# CH32M030K8U7-R0.net
KiCad netlist of a schematic drawn in Altium Designer
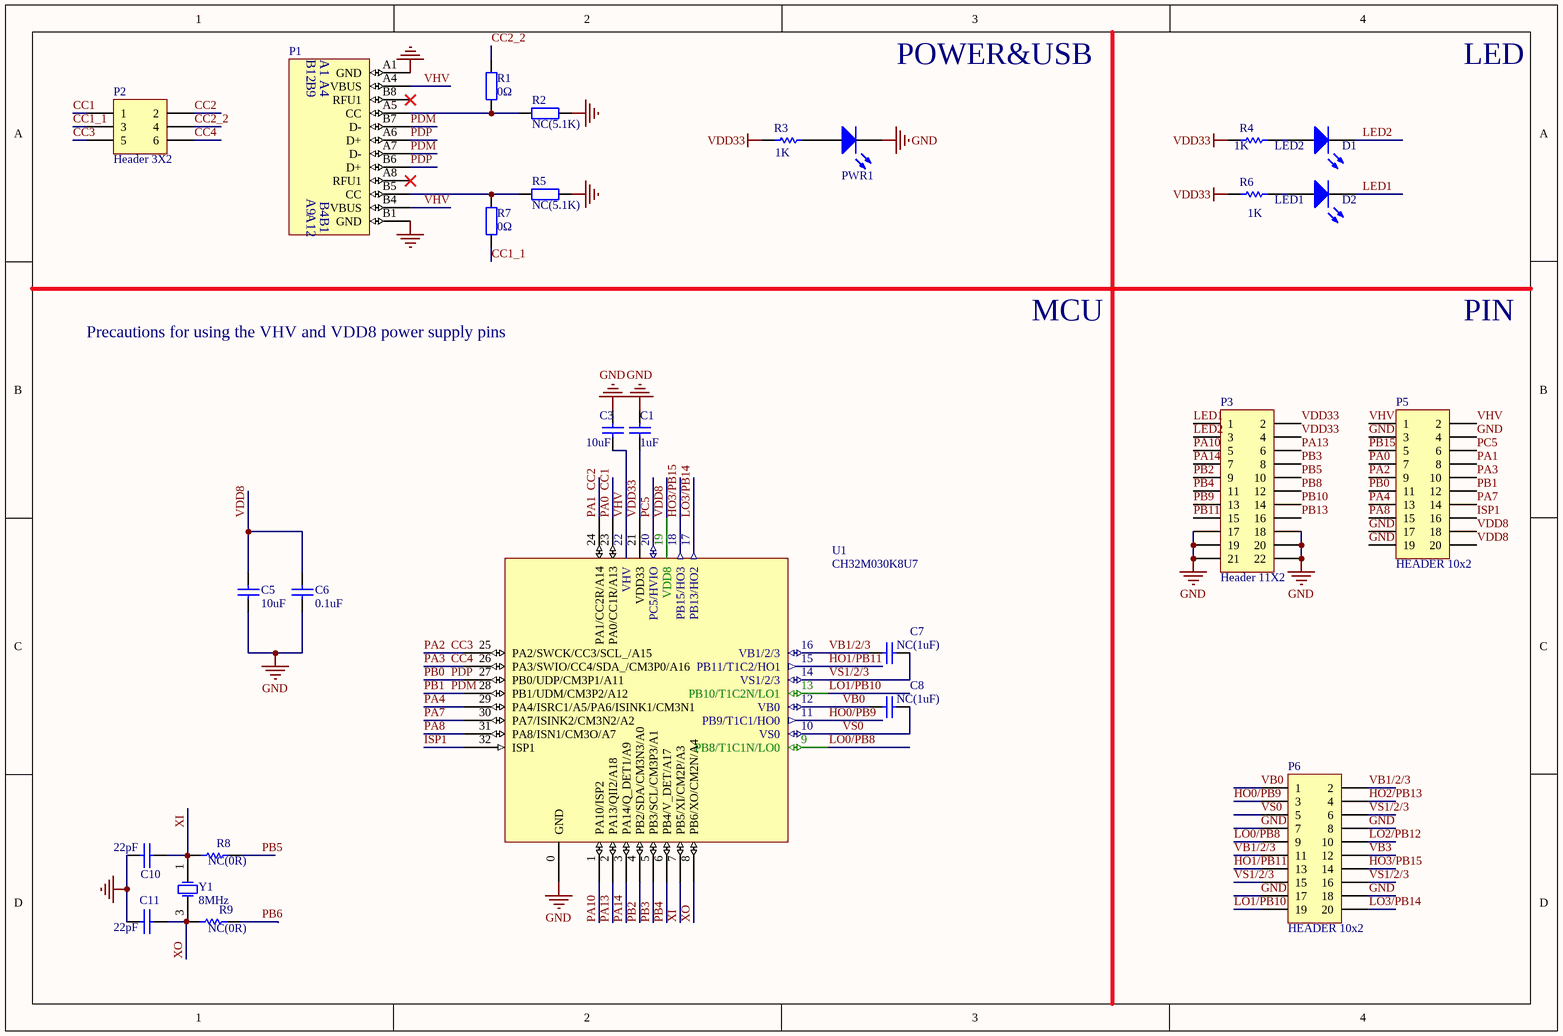
[diagram p0: CH32M030K8U7-R0.SchDoc]

(export (version "E")
  (design (tool "Eeschema 10.0.6"))
  (components
    (comp (ref "C1")
      (value "1uF")
      (footprint "0603_C")
      (description "Capacitor")
      (fields (field (name "PUBLISHER") "Altium Limited"))
      (libsource (lib "*") (part "Cap"))
    )
    (comp (ref "C3")
      (value "10uF")
      (footprint "0603_C")
      (description "Capacitor")
      (fields (field (name "PUBLISHER") "Altium Limited"))
      (libsource (lib "*") (part "Cap"))
    )
    (comp (ref "C5")
      (value "10uF")
      (footprint "0603_C")
      (description "Capacitor")
      (fields (field (name "PUBLISHER") "Altium Limited"))
      (libsource (lib "*") (part "Cap"))
    )
    (comp (ref "C6")
      (value "0.1uF")
      (footprint "0603_C")
      (description "Capacitor")
      (fields (field (name "PUBLISHER") "Altium Limited"))
      (libsource (lib "*") (part "Cap"))
    )
    (comp (ref "C7")
      (value "NC(1uF)")
      (footprint "0603_C")
      (description "Capacitor")
      (fields (field (name "PUBLISHER") "Altium Limited"))
      (libsource (lib "*") (part "Cap"))
    )
    (comp (ref "C8")
      (value "NC(1uF)")
      (footprint "0603_C")
      (description "Capacitor")
      (fields (field (name "PUBLISHER") "Altium Limited"))
      (libsource (lib "*") (part "Cap"))
    )
    (comp (ref "C10")
      (value "22pF")
      (footprint "0603_C")
      (description "Capacitor")
      (libsource (lib "*") (part "CAP"))
    )
    (comp (ref "C11")
      (value "22pF")
      (footprint "0603_C")
      (description "Capacitor")
      (libsource (lib "*") (part "CAP"))
    )
    (comp (ref "D1")
      (value "LED2")
      (footprint "0603+")
      (description "Typical INFRARED GaAs LED")
      (fields (field (name "PUBLISHER") "Altium Limited"))
      (libsource (lib "*") (part "LED0"))
    )
    (comp (ref "D2")
      (value "LED1")
      (footprint "0603+")
      (description "Typical INFRARED GaAs LED")
      (fields (field (name "PUBLISHER") "Altium Limited"))
      (libsource (lib "*") (part "LED0"))
    )
    (comp (ref "P1")
      (value "TYPE-C")
      (footprint "TYPE-C-Receptacle-2.0")
      (libsource (lib "*") (part "TYPE-C1"))
    )
    (comp (ref "P2")
      (value "Header 3X2")
      (footprint "IDC6-2.54mm")
      (description "Header, 3-Pin, Dual row")
      (fields (field (name "PUBLISHER") "Altium Limited"))
      (libsource (lib "Miscellaneous Connectors") (part "Header 3X2"))
    )
    (comp (ref "P3")
      (value "Header 11X2")
      (footprint "IDC22-2.54mm")
      (description "Header, 11-Pin, Dual row")
      (fields (field (name "PUBLISHER") "Altium Limited"))
      (libsource (lib "Miscellaneous Connectors") (part "Header 11X2"))
    )
    (comp (ref "P5")
      (value "HEADER 10x2")
      (footprint "MYPCB:IDC20-2.54MM")
      (description "Header, 10-Pin, Dual row")
      (libsource (lib "wch_sch_others") (part "HEADER 10x2"))
    )
    (comp (ref "P6")
      (value "HEADER 10x2")
      (footprint "MYPCB:IDC20-2.54MM")
      (description "Header, 10-Pin, Dual row")
      (libsource (lib "wch_sch_others") (part "HEADER 10x2"))
    )
    (comp (ref "PWR1")
      (value "POWER  red")
      (footprint "0603+")
      (description "Typical INFRARED GaAs LED")
      (fields (field (name "PUBLISHER") "Altium Limited"))
      (libsource (lib "*") (part "LED0"))
    )
    (comp (ref "R1")
      (value "0Ω")
      (footprint "0603")
      (description "Resistor")
      (libsource (lib "Miscellaneous Devices") (part "Res2"))
    )
    (comp (ref "R2")
      (value "NC(5.1K)")
      (footprint "0603")
      (description "Resistor")
      (libsource (lib "") (part "Res2_1"))
    )
    (comp (ref "R3")
      (value "1K")
      (footprint "0603")
      (description "Semiconductor Resistor")
      (fields (field (name "PUBLISHER") "Altium Limited"))
      (libsource (lib "*") (part "Res Semi"))
    )
    (comp (ref "R4")
      (value "1K")
      (footprint "0603")
      (description "Semiconductor Resistor")
      (fields (field (name "PUBLISHER") "Altium Limited"))
      (libsource (lib "*") (part "Res Semi"))
    )
    (comp (ref "R5")
      (value "NC(5.1K)")
      (footprint "0603")
      (description "Resistor")
      (libsource (lib "") (part "Res2_1"))
    )
    (comp (ref "R6")
      (value "1K")
      (footprint "0603")
      (description "Semiconductor Resistor")
      (fields (field (name "PUBLISHER") "Altium Limited"))
      (libsource (lib "*") (part "Res Semi"))
    )
    (comp (ref "R7")
      (value "0Ω")
      (footprint "0603")
      (description "Resistor")
      (libsource (lib "Miscellaneous Devices") (part "Res2"))
    )
    (comp (ref "R8")
      (value "NC(0R)")
      (footprint "0603")
      (description "Semiconductor Resistor")
      (fields (field (name "PUBLISHER") "Altium Limited"))
      (libsource (lib "*") (part "Res Semi"))
    )
    (comp (ref "R9")
      (value "NC(0R)")
      (footprint "0603")
      (description "Semiconductor Resistor")
      (fields (field (name "PUBLISHER") "Altium Limited"))
      (libsource (lib "*") (part "Res Semi"))
    )
    (comp (ref "U1")
      (value "CH32M030K8U7")
      (footprint "QFN32_4X4")
      (description "RISC-V MCU, 72MHz, USB, Type-C/PD, OPA, CMP, 28V gate driver")
      (libsource (lib "CHXXX") (part "CH32M030K8U7"))
    )
    (comp (ref "Y1")
      (value "8MHz")
      (footprint "XT3225")
      (description "Crystal Oscillator")
      (fields (field (name "PUBLISHER") "Altium Limited"))
      (libsource (lib "*") (part "XTAL"))
    )
  )
  (nets
    (net (code "1") (name "/CC1") (class "Default")
      (node (ref "P2") (pin "1") (pinfunction "1_1") (pintype "passive"))
      (node (ref "P5") (pin "7") (pinfunction "7_7") (pintype "passive"))
      (node (ref "U1") (pin "23") (pinfunction "PA0/CC1R/A13_23") (pintype "bidirectional"))
    )
    (net (code "2") (name "/CC1_1") (class "Default")
      (node (ref "P2") (pin "3") (pinfunction "3_3") (pintype "passive"))
      (node (ref "R7") (pin "1") (pinfunction "1_1") (pintype "passive"))
    )
    (net (code "3") (name "/CC2") (class "Default")
      (node (ref "P2") (pin "2") (pinfunction "2_2") (pintype "passive"))
      (node (ref "P5") (pin "8") (pinfunction "8_8") (pintype "passive"))
      (node (ref "U1") (pin "24") (pinfunction "PA1/CC2R/A14_24") (pintype "bidirectional"))
    )
    (net (code "4") (name "/CC2_2") (class "Default")
      (node (ref "P2") (pin "4") (pinfunction "4_4") (pintype "passive"))
      (node (ref "R1") (pin "2") (pinfunction "2_2") (pintype "passive"))
    )
    (net (code "5") (name "/CC3") (class "Default")
      (node (ref "P2") (pin "5") (pinfunction "5_5") (pintype "passive"))
      (node (ref "P5") (pin "9") (pinfunction "9_9") (pintype "passive"))
      (node (ref "U1") (pin "25") (pinfunction "PA2/SWCK/CC3/SCL_/A15_25") (pintype "bidirectional"))
    )
    (net (code "6") (name "/CC4") (class "Default")
      (node (ref "P2") (pin "6") (pinfunction "6_6") (pintype "passive"))
      (node (ref "P5") (pin "10") (pinfunction "10_10") (pintype "passive"))
      (node (ref "U1") (pin "26") (pinfunction "PA3/SWIO/CC4/SDA_/CM3P0/A16_26") (pintype "bidirectional"))
    )
    (net (code "7") (name "/HO0{slash}PB9") (class "Default")
      (node (ref "P6") (pin "3") (pinfunction "3_3") (pintype "passive"))
      (node (ref "U1") (pin "11") (pinfunction "PB9/T1C1/HO0_11") (pintype "output"))
    )
    (net (code "8") (name "/HO1{slash}PB11") (class "Default")
      (node (ref "P6") (pin "13") (pinfunction "13_13") (pintype "passive"))
      (node (ref "U1") (pin "15") (pinfunction "PB11/T1C2/HO1_15") (pintype "output"))
    )
    (net (code "9") (name "/HO2{slash}PB13") (class "Default")
      (node (ref "P6") (pin "4") (pinfunction "4_4") (pintype "passive"))
    )
    (net (code "10") (name "/HO3{slash}PB15") (class "Default")
      (node (ref "P6") (pin "14") (pinfunction "14_14") (pintype "passive"))
      (node (ref "U1") (pin "18") (pinfunction "PB15/HO3_18") (pintype "output"))
    )
    (net (code "11") (name "/ISP1") (class "Default")
      (node (ref "P5") (pin "16") (pinfunction "16_16") (pintype "passive"))
      (node (ref "U1") (pin "32") (pinfunction "ISP1_32") (pintype "input"))
    )
    (net (code "12") (name "/LED1") (class "Default")
      (node (ref "D2") (pin "2") (pinfunction "K_2") (pintype "passive"))
      (node (ref "P3") (pin "1") (pinfunction "1_1") (pintype "passive"))
    )
    (net (code "13") (name "/LED2") (class "Default")
      (node (ref "D1") (pin "2") (pinfunction "K_2") (pintype "passive"))
      (node (ref "P3") (pin "3") (pinfunction "3_3") (pintype "passive"))
    )
    (net (code "14") (name "/LO0{slash}PB8") (class "Default")
      (node (ref "P6") (pin "9") (pinfunction "9_9") (pintype "passive"))
      (node (ref "U1") (pin "9") (pinfunction "PB8/T1C1N/LO0_9") (pintype "bidirectional"))
    )
    (net (code "15") (name "/LO1{slash}PB10") (class "Default")
      (node (ref "P6") (pin "19") (pinfunction "19_19") (pintype "passive"))
      (node (ref "U1") (pin "13") (pinfunction "PB10/T1C2N/LO1_13") (pintype "bidirectional"))
    )
    (net (code "16") (name "/LO2{slash}PB12") (class "Default")
      (node (ref "P6") (pin "10") (pinfunction "10_10") (pintype "passive"))
    )
    (net (code "17") (name "/LO3{slash}PB14") (class "Default")
      (node (ref "P6") (pin "20") (pinfunction "20_20") (pintype "passive"))
      (node (ref "U1") (pin "17") (pinfunction "PB13/HO2_17") (pintype "output"))
    )
    (net (code "18") (name "/PA4") (class "Default")
      (node (ref "P5") (pin "13") (pinfunction "13_13") (pintype "passive"))
      (node (ref "U1") (pin "29") (pinfunction "PA4/ISRC1/A5/PA6/ISINK1/CM3N1_29") (pintype "bidirectional"))
    )
    (net (code "19") (name "/PA7") (class "Default")
      (node (ref "P5") (pin "14") (pinfunction "14_14") (pintype "passive"))
      (node (ref "U1") (pin "30") (pinfunction "PA7/ISINK2/CM3N2/A2_30") (pintype "bidirectional"))
    )
    (net (code "20") (name "/PA8") (class "Default")
      (node (ref "P5") (pin "15") (pinfunction "15_15") (pintype "passive"))
      (node (ref "U1") (pin "31") (pinfunction "PA8/ISN1/CM3O/A7_31") (pintype "bidirectional"))
    )
    (net (code "21") (name "/PA10") (class "Default")
      (node (ref "P3") (pin "5") (pinfunction "5_5") (pintype "passive"))
      (node (ref "U1") (pin "1") (pinfunction "PA10/ISP2_1") (pintype "bidirectional"))
    )
    (net (code "22") (name "/PA13") (class "Default")
      (node (ref "P3") (pin "6") (pinfunction "6_6") (pintype "passive"))
      (node (ref "U1") (pin "2") (pinfunction "PA13/QII2/A18_2") (pintype "bidirectional"))
    )
    (net (code "23") (name "/PA14") (class "Default")
      (node (ref "P3") (pin "7") (pinfunction "7_7") (pintype "passive"))
      (node (ref "U1") (pin "3") (pinfunction "PA14/Q_DET1/A9_3") (pintype "bidirectional"))
    )
    (net (code "24") (name "/PB0") (class "Default")
      (node (ref "P1") (pin "A6") (pinfunction "D+_A6") (pintype "bidirectional"))
      (node (ref "P1") (pin "B6") (pinfunction "D+_B6") (pintype "bidirectional"))
      (node (ref "P5") (pin "11") (pinfunction "11_11") (pintype "passive"))
      (node (ref "U1") (pin "27") (pinfunction "PB0/UDP/CM3P1/A11_27") (pintype "bidirectional"))
    )
    (net (code "25") (name "/PB1") (class "Default")
      (node (ref "P1") (pin "A7") (pinfunction "D-_A7") (pintype "bidirectional"))
      (node (ref "P1") (pin "B7") (pinfunction "D-_B7") (pintype "bidirectional"))
      (node (ref "P5") (pin "12") (pinfunction "12_12") (pintype "passive"))
      (node (ref "U1") (pin "28") (pinfunction "PB1/UDM/CM3P2/A12_28") (pintype "bidirectional"))
    )
    (net (code "26") (name "/PB2") (class "Default")
      (node (ref "P3") (pin "9") (pinfunction "9_9") (pintype "passive"))
      (node (ref "U1") (pin "4") (pinfunction "PB2/SDA/CM3N3/A0_4") (pintype "bidirectional"))
    )
    (net (code "27") (name "/PB3") (class "Default")
      (node (ref "P3") (pin "8") (pinfunction "8_8") (pintype "passive"))
      (node (ref "U1") (pin "5") (pinfunction "PB3/SCL/CM3P3/A1_5") (pintype "bidirectional"))
    )
    (net (code "28") (name "/PB4") (class "Default")
      (node (ref "P3") (pin "11") (pinfunction "11_11") (pintype "passive"))
      (node (ref "U1") (pin "6") (pinfunction "PB4/V_DET/A17_6") (pintype "bidirectional"))
    )
    (net (code "29") (name "/PB5") (class "Default")
      (node (ref "P3") (pin "10") (pinfunction "10_10") (pintype "passive"))
      (node (ref "R8") (pin "2") (pinfunction "2_2") (pintype "passive"))
    )
    (net (code "30") (name "/PB6") (class "Default")
      (node (ref "R9") (pin "2") (pinfunction "2_2") (pintype "passive"))
    )
    (net (code "31") (name "/PB8") (class "Default")
      (node (ref "P3") (pin "12") (pinfunction "12_12") (pintype "passive"))
    )
    (net (code "32") (name "/PB9") (class "Default")
      (node (ref "P3") (pin "13") (pinfunction "13_13") (pintype "passive"))
    )
    (net (code "33") (name "/PB10") (class "Default")
      (node (ref "P3") (pin "14") (pinfunction "14_14") (pintype "passive"))
    )
    (net (code "34") (name "/PB11") (class "Default")
      (node (ref "P3") (pin "15") (pinfunction "15_15") (pintype "passive"))
    )
    (net (code "35") (name "/PB13") (class "Default")
      (node (ref "P3") (pin "16") (pinfunction "16_16") (pintype "passive"))
    )
    (net (code "36") (name "/PB15") (class "Default")
      (node (ref "P5") (pin "5") (pinfunction "5_5") (pintype "passive"))
    )
    (net (code "37") (name "/PC5") (class "Default")
      (node (ref "P5") (pin "6") (pinfunction "6_6") (pintype "passive"))
      (node (ref "U1") (pin "20") (pinfunction "PC5/HVIO_20") (pintype "bidirectional"))
    )
    (net (code "38") (name "/VB0") (class "Default")
      (node (ref "C8") (pin "2") (pinfunction "2_2") (pintype "passive"))
      (node (ref "P6") (pin "1") (pinfunction "1_1") (pintype "passive"))
      (node (ref "U1") (pin "12") (pinfunction "VB0_12") (pintype "bidirectional"))
    )
    (net (code "39") (name "/VB1{slash}2{slash}3") (class "Default")
      (node (ref "C7") (pin "2") (pinfunction "2_2") (pintype "passive"))
      (node (ref "P6") (pin "11") (pinfunction "11_11") (pintype "passive"))
      (node (ref "P6") (pin "2") (pinfunction "2_2") (pintype "passive"))
      (node (ref "U1") (pin "16") (pinfunction "VB1/2/3_16") (pintype "bidirectional"))
    )
    (net (code "40") (name "/VB3") (class "Default")
      (node (ref "P6") (pin "12") (pinfunction "12_12") (pintype "passive"))
    )
    (net (code "41") (name "/VDD8") (class "Default")
      (node (ref "C5") (pin "2") (pinfunction "2_2") (pintype "passive"))
      (node (ref "C6") (pin "2") (pinfunction "2_2") (pintype "passive"))
      (node (ref "P5") (pin "18") (pinfunction "18_18") (pintype "passive"))
      (node (ref "P5") (pin "20") (pinfunction "20_20") (pintype "passive"))
      (node (ref "U1") (pin "19") (pinfunction "VDD8_19") (pintype "power_in"))
    )
    (net (code "42") (name "/VHV") (class "Default")
      (node (ref "C3") (pin "1") (pinfunction "1_1") (pintype "passive"))
      (node (ref "P1") (pin "A4") (pinfunction "VBUS_A4") (pintype "bidirectional"))
      (node (ref "P1") (pin "B4") (pinfunction "VBUS_B4") (pintype "bidirectional"))
      (node (ref "P5") (pin "1") (pinfunction "1_1") (pintype "passive"))
      (node (ref "P5") (pin "2") (pinfunction "2_2") (pintype "passive"))
      (node (ref "U1") (pin "22") (pinfunction "VHV_22") (pintype "power_in"))
    )
    (net (code "43") (name "/VS0") (class "Default")
      (node (ref "C8") (pin "1") (pinfunction "1_1") (pintype "passive"))
      (node (ref "P6") (pin "5") (pinfunction "5_5") (pintype "passive"))
      (node (ref "U1") (pin "10") (pinfunction "VS0_10") (pintype "bidirectional"))
    )
    (net (code "44") (name "/VS1{slash}2{slash}3") (class "Default")
      (node (ref "C7") (pin "1") (pinfunction "1_1") (pintype "passive"))
      (node (ref "P6") (pin "15") (pinfunction "15_15") (pintype "passive"))
      (node (ref "P6") (pin "16") (pinfunction "16_16") (pintype "passive"))
      (node (ref "P6") (pin "6") (pinfunction "6_6") (pintype "passive"))
      (node (ref "U1") (pin "14") (pinfunction "VS1/2/3_14") (pintype "bidirectional"))
    )
    (net (code "45") (name "/XI") (class "Default")
      (node (ref "C10") (pin "2") (pinfunction "2_2") (pintype "passive"))
      (node (ref "R8") (pin "1") (pinfunction "1_1") (pintype "passive"))
      (node (ref "U1") (pin "7") (pinfunction "PB5/XI/CM2P/A3_7") (pintype "bidirectional"))
      (node (ref "Y1") (pin "1") (pinfunction "OSC1_1") (pintype "passive"))
    )
    (net (code "46") (name "/XO") (class "Default")
      (node (ref "C11") (pin "2") (pinfunction "2_2") (pintype "passive"))
      (node (ref "R9") (pin "1") (pinfunction "1_1") (pintype "passive"))
      (node (ref "U1") (pin "8") (pinfunction "PB6/XO/CM2N/A4_8") (pintype "bidirectional"))
    )
    (net (code "47") (name "GND") (class "Default")
      (node (ref "C1") (pin "2") (pinfunction "2_2") (pintype "passive"))
      (node (ref "C10") (pin "1") (pinfunction "1_1") (pintype "passive"))
      (node (ref "C11") (pin "1") (pinfunction "1_1") (pintype "passive"))
      (node (ref "C3") (pin "2") (pinfunction "2_2") (pintype "passive"))
      (node (ref "C5") (pin "1") (pinfunction "1_1") (pintype "passive"))
      (node (ref "C6") (pin "1") (pinfunction "1_1") (pintype "passive"))
      (node (ref "P1") (pin "A1") (pinfunction "GND_A1") (pintype "bidirectional"))
      (node (ref "P1") (pin "B1") (pinfunction "GND_B1") (pintype "bidirectional"))
      (node (ref "P3") (pin "17") (pinfunction "17_17") (pintype "passive"))
      (node (ref "P3") (pin "18") (pinfunction "18_18") (pintype "passive"))
      (node (ref "P3") (pin "19") (pinfunction "19_19") (pintype "passive"))
      (node (ref "P3") (pin "20") (pinfunction "20_20") (pintype "passive"))
      (node (ref "P3") (pin "21") (pinfunction "21_21") (pintype "passive"))
      (node (ref "P3") (pin "22") (pinfunction "22_22") (pintype "passive"))
      (node (ref "P5") (pin "17") (pinfunction "17_17") (pintype "passive"))
      (node (ref "P5") (pin "19") (pinfunction "19_19") (pintype "passive"))
      (node (ref "P5") (pin "3") (pinfunction "3_3") (pintype "passive"))
      (node (ref "P5") (pin "4") (pinfunction "4_4") (pintype "passive"))
      (node (ref "P6") (pin "17") (pinfunction "17_17") (pintype "passive"))
      (node (ref "P6") (pin "18") (pinfunction "18_18") (pintype "passive"))
      (node (ref "P6") (pin "7") (pinfunction "7_7") (pintype "passive"))
      (node (ref "P6") (pin "8") (pinfunction "8_8") (pintype "passive"))
      (node (ref "PWR1") (pin "2") (pinfunction "K_2") (pintype "passive"))
      (node (ref "R2") (pin "2") (pinfunction "2_2") (pintype "passive"))
      (node (ref "R5") (pin "2") (pinfunction "2_2") (pintype "passive"))
      (node (ref "U1") (pin "0") (pinfunction "GND_0") (pintype "power_in"))
    )
    (net (code "48") (name "Net-(D1-A)") (class "Default")
      (node (ref "D1") (pin "1") (pinfunction "A_1") (pintype "passive"))
      (node (ref "R4") (pin "2") (pinfunction "2_2") (pintype "passive"))
    )
    (net (code "49") (name "Net-(D2-A)") (class "Default")
      (node (ref "D2") (pin "1") (pinfunction "A_1") (pintype "passive"))
      (node (ref "R6") (pin "2") (pinfunction "2_2") (pintype "passive"))
    )
    (net (code "50") (name "Net-(P1-CC-PadA5)") (class "Default")
      (node (ref "P1") (pin "A5") (pinfunction "CC_A5") (pintype "bidirectional"))
      (node (ref "R1") (pin "1") (pinfunction "1_1") (pintype "passive"))
      (node (ref "R2") (pin "1") (pinfunction "1_1") (pintype "passive"))
    )
    (net (code "51") (name "Net-(P1-CC-PadB5)") (class "Default")
      (node (ref "P1") (pin "B5") (pinfunction "CC_B5") (pintype "bidirectional"))
      (node (ref "R5") (pin "1") (pinfunction "1_1") (pintype "passive"))
      (node (ref "R7") (pin "2") (pinfunction "2_2") (pintype "passive"))
    )
    (net (code "52") (name "Net-(PWR1-A)") (class "Default")
      (node (ref "PWR1") (pin "1") (pinfunction "A_1") (pintype "passive"))
      (node (ref "R3") (pin "1") (pinfunction "1_1") (pintype "passive"))
    )
    (net (code "53") (name "VDD33") (class "Default")
      (node (ref "C1") (pin "1") (pinfunction "1_1") (pintype "passive"))
      (node (ref "P3") (pin "2") (pinfunction "2_2") (pintype "passive"))
      (node (ref "P3") (pin "4") (pinfunction "4_4") (pintype "passive"))
      (node (ref "R3") (pin "2") (pinfunction "2_2") (pintype "passive"))
      (node (ref "R4") (pin "1") (pinfunction "1_1") (pintype "passive"))
      (node (ref "R6") (pin "1") (pinfunction "1_1") (pintype "passive"))
      (node (ref "U1") (pin "21") (pinfunction "VDD33_21") (pintype "power_in"))
    )
    (net (code "54") (name "unconnected-(P1-RFU1-PadA8)") (class "Default")
      (node (ref "P1") (pin "A8") (pinfunction "RFU1_A8") (pintype "bidirectional+no_connect"))
    )
    (net (code "55") (name "unconnected-(P1-RFU1-PadB8)") (class "Default")
      (node (ref "P1") (pin "B8") (pinfunction "RFU1_B8") (pintype "bidirectional+no_connect"))
    )
    (net (code "56") (name "unconnected-(Y1-OSC2-Pad3)") (class "Default")
      (node (ref "Y1") (pin "3") (pinfunction "OSC2_3") (pintype "passive"))
    )
  )
)
